# led_2835_curve_45X45cm.net
KiCad netlist of a schematic drawn in Altium Designer
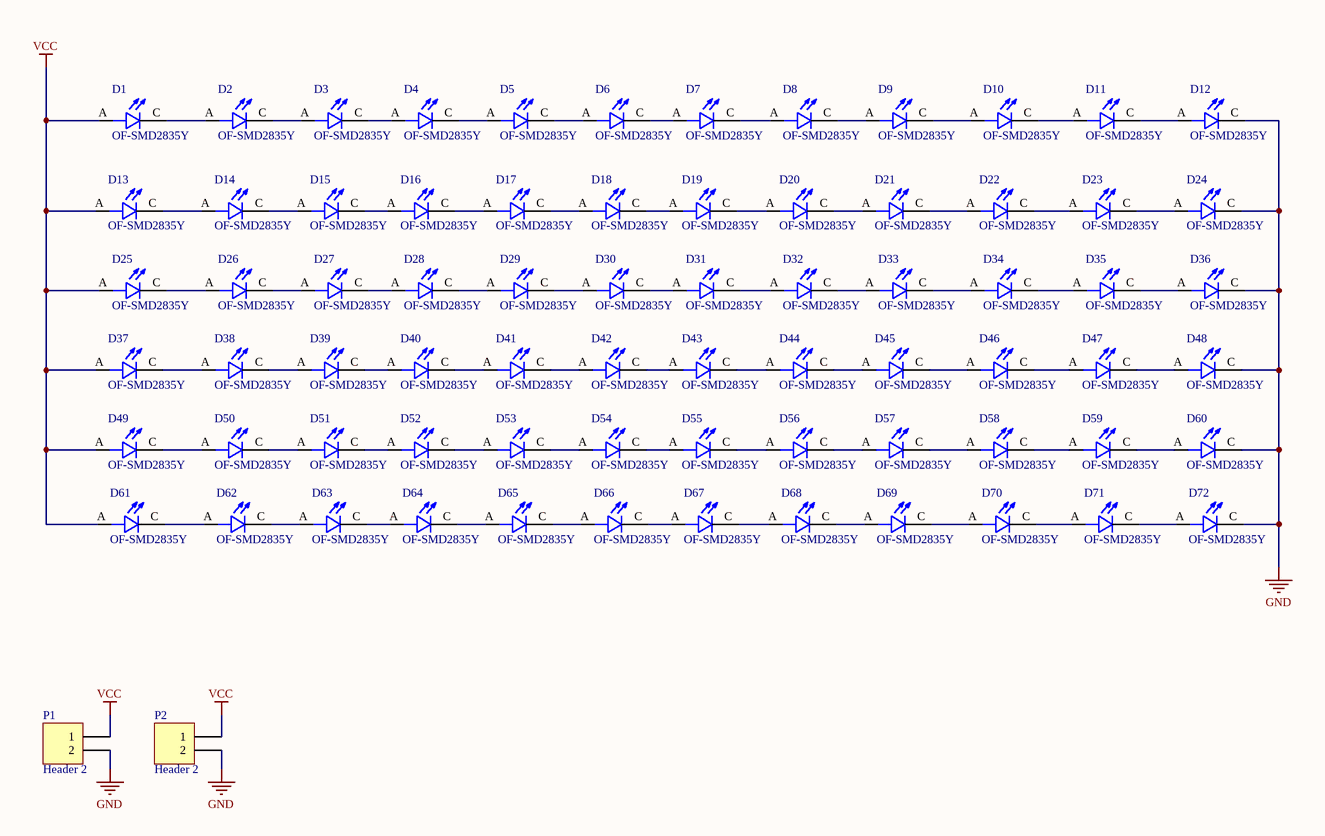
[diagram p0: led_2835_curve_45X45cm.SchDoc]

(export (version "E")
  (design (tool "Eeschema 10.0.6"))
  (components
    (comp (ref "D1")
      (value "OF-SMD2835Y")
      (footprint "LED_OF-SMD2835Y")
      (description "LED; SMD; 2835, PLCC2; yellow; 2200-2800mcd; 2.8x3.5x0.75mm; 120Â°")
      (libsource (lib "") (part "OF-SMD2835Y_3"))
    )
    (comp (ref "D2")
      (value "OF-SMD2835Y")
      (footprint "LED_OF-SMD2835Y")
      (description "LED; SMD; 2835, PLCC2; yellow; 2200-2800mcd; 2.8x3.5x0.75mm; 120Â°")
      (libsource (lib "") (part "OF-SMD2835Y_3"))
    )
    (comp (ref "D3")
      (value "OF-SMD2835Y")
      (footprint "LED_OF-SMD2835Y")
      (description "LED; SMD; 2835, PLCC2; yellow; 2200-2800mcd; 2.8x3.5x0.75mm; 120Â°")
      (libsource (lib "") (part "OF-SMD2835Y_3"))
    )
    (comp (ref "D4")
      (value "OF-SMD2835Y")
      (footprint "LED_OF-SMD2835Y")
      (description "LED; SMD; 2835, PLCC2; yellow; 2200-2800mcd; 2.8x3.5x0.75mm; 120Â°")
      (libsource (lib "") (part "OF-SMD2835Y_3"))
    )
    (comp (ref "D5")
      (value "OF-SMD2835Y")
      (footprint "LED_OF-SMD2835Y")
      (description "LED; SMD; 2835, PLCC2; yellow; 2200-2800mcd; 2.8x3.5x0.75mm; 120Â°")
      (libsource (lib "") (part "OF-SMD2835Y_3"))
    )
    (comp (ref "D6")
      (value "OF-SMD2835Y")
      (footprint "LED_OF-SMD2835Y")
      (description "LED; SMD; 2835, PLCC2; yellow; 2200-2800mcd; 2.8x3.5x0.75mm; 120Â°")
      (libsource (lib "") (part "OF-SMD2835Y_1"))
    )
    (comp (ref "D7")
      (value "OF-SMD2835Y")
      (footprint "LED_OF-SMD2835Y")
      (description "LED; SMD; 2835, PLCC2; yellow; 2200-2800mcd; 2.8x3.5x0.75mm; 120Â°")
      (libsource (lib "") (part "OF-SMD2835Y_1"))
    )
    (comp (ref "D8")
      (value "OF-SMD2835Y")
      (footprint "LED_OF-SMD2835Y")
      (description "LED; SMD; 2835, PLCC2; yellow; 2200-2800mcd; 2.8x3.5x0.75mm; 120Â°")
      (libsource (lib "") (part "OF-SMD2835Y_1"))
    )
    (comp (ref "D9")
      (value "OF-SMD2835Y")
      (footprint "LED_OF-SMD2835Y")
      (description "LED; SMD; 2835, PLCC2; yellow; 2200-2800mcd; 2.8x3.5x0.75mm; 120Â°")
      (libsource (lib "") (part "OF-SMD2835Y_1"))
    )
    (comp (ref "D10")
      (value "OF-SMD2835Y")
      (footprint "LED_OF-SMD2835Y")
      (description "LED; SMD; 2835, PLCC2; yellow; 2200-2800mcd; 2.8x3.5x0.75mm; 120Â°")
      (libsource (lib "") (part "OF-SMD2835Y_1"))
    )
    (comp (ref "D11")
      (value "OF-SMD2835Y")
      (footprint "LED_OF-SMD2835Y")
      (description "LED; SMD; 2835, PLCC2; yellow; 2200-2800mcd; 2.8x3.5x0.75mm; 120Â°")
      (libsource (lib "") (part "OF-SMD2835Y_1"))
    )
    (comp (ref "D12")
      (value "OF-SMD2835Y")
      (footprint "LED_OF-SMD2835Y")
      (description "LED; SMD; 2835, PLCC2; yellow; 2200-2800mcd; 2.8x3.5x0.75mm; 120Â°")
      (libsource (lib "") (part "OF-SMD2835Y_1"))
    )
    (comp (ref "D13")
      (value "OF-SMD2835Y")
      (footprint "LED_OF-SMD2835Y")
      (description "LED; SMD; 2835, PLCC2; yellow; 2200-2800mcd; 2.8x3.5x0.75mm; 120Â°")
      (libsource (lib "OF-SMD2835Y") (part "OF-SMD2835Y"))
    )
    (comp (ref "D14")
      (value "OF-SMD2835Y")
      (footprint "LED_OF-SMD2835Y")
      (description "LED; SMD; 2835, PLCC2; yellow; 2200-2800mcd; 2.8x3.5x0.75mm; 120Â°")
      (libsource (lib "OF-SMD2835Y") (part "OF-SMD2835Y"))
    )
    (comp (ref "D15")
      (value "OF-SMD2835Y")
      (footprint "LED_OF-SMD2835Y")
      (description "LED; SMD; 2835, PLCC2; yellow; 2200-2800mcd; 2.8x3.5x0.75mm; 120Â°")
      (libsource (lib "OF-SMD2835Y") (part "OF-SMD2835Y"))
    )
    (comp (ref "D16")
      (value "OF-SMD2835Y")
      (footprint "LED_OF-SMD2835Y")
      (description "LED; SMD; 2835, PLCC2; yellow; 2200-2800mcd; 2.8x3.5x0.75mm; 120Â°")
      (libsource (lib "OF-SMD2835Y") (part "OF-SMD2835Y"))
    )
    (comp (ref "D17")
      (value "OF-SMD2835Y")
      (footprint "LED_OF-SMD2835Y")
      (description "LED; SMD; 2835, PLCC2; yellow; 2200-2800mcd; 2.8x3.5x0.75mm; 120Â°")
      (libsource (lib "OF-SMD2835Y") (part "OF-SMD2835Y"))
    )
    (comp (ref "D18")
      (value "OF-SMD2835Y")
      (footprint "LED_OF-SMD2835Y")
      (description "LED; SMD; 2835, PLCC2; yellow; 2200-2800mcd; 2.8x3.5x0.75mm; 120Â°")
      (libsource (lib "") (part "OF-SMD2835Y_2"))
    )
    (comp (ref "D19")
      (value "OF-SMD2835Y")
      (footprint "LED_OF-SMD2835Y")
      (description "LED; SMD; 2835, PLCC2; yellow; 2200-2800mcd; 2.8x3.5x0.75mm; 120Â°")
      (libsource (lib "") (part "OF-SMD2835Y_2"))
    )
    (comp (ref "D20")
      (value "OF-SMD2835Y")
      (footprint "LED_OF-SMD2835Y")
      (description "LED; SMD; 2835, PLCC2; yellow; 2200-2800mcd; 2.8x3.5x0.75mm; 120Â°")
      (libsource (lib "") (part "OF-SMD2835Y_2"))
    )
    (comp (ref "D21")
      (value "OF-SMD2835Y")
      (footprint "LED_OF-SMD2835Y")
      (description "LED; SMD; 2835, PLCC2; yellow; 2200-2800mcd; 2.8x3.5x0.75mm; 120Â°")
      (libsource (lib "") (part "OF-SMD2835Y_2"))
    )
    (comp (ref "D22")
      (value "OF-SMD2835Y")
      (footprint "LED_OF-SMD2835Y")
      (description "LED; SMD; 2835, PLCC2; yellow; 2200-2800mcd; 2.8x3.5x0.75mm; 120Â°")
      (libsource (lib "") (part "OF-SMD2835Y_2"))
    )
    (comp (ref "D23")
      (value "OF-SMD2835Y")
      (footprint "LED_OF-SMD2835Y")
      (description "LED; SMD; 2835, PLCC2; yellow; 2200-2800mcd; 2.8x3.5x0.75mm; 120Â°")
      (libsource (lib "") (part "OF-SMD2835Y_2"))
    )
    (comp (ref "D24")
      (value "OF-SMD2835Y")
      (footprint "LED_OF-SMD2835Y")
      (description "LED; SMD; 2835, PLCC2; yellow; 2200-2800mcd; 2.8x3.5x0.75mm; 120Â°")
      (libsource (lib "") (part "OF-SMD2835Y_2"))
    )
    (comp (ref "D25")
      (value "OF-SMD2835Y")
      (footprint "LED_OF-SMD2835Y")
      (description "LED; SMD; 2835, PLCC2; yellow; 2200-2800mcd; 2.8x3.5x0.75mm; 120Â°")
      (libsource (lib "OF-SMD2835Y") (part "OF-SMD2835Y"))
    )
    (comp (ref "D26")
      (value "OF-SMD2835Y")
      (footprint "LED_OF-SMD2835Y")
      (description "LED; SMD; 2835, PLCC2; yellow; 2200-2800mcd; 2.8x3.5x0.75mm; 120Â°")
      (libsource (lib "OF-SMD2835Y") (part "OF-SMD2835Y"))
    )
    (comp (ref "D27")
      (value "OF-SMD2835Y")
      (footprint "LED_OF-SMD2835Y")
      (description "LED; SMD; 2835, PLCC2; yellow; 2200-2800mcd; 2.8x3.5x0.75mm; 120Â°")
      (libsource (lib "OF-SMD2835Y") (part "OF-SMD2835Y"))
    )
    (comp (ref "D28")
      (value "OF-SMD2835Y")
      (footprint "LED_OF-SMD2835Y")
      (description "LED; SMD; 2835, PLCC2; yellow; 2200-2800mcd; 2.8x3.5x0.75mm; 120Â°")
      (libsource (lib "OF-SMD2835Y") (part "OF-SMD2835Y"))
    )
    (comp (ref "D29")
      (value "OF-SMD2835Y")
      (footprint "LED_OF-SMD2835Y")
      (description "LED; SMD; 2835, PLCC2; yellow; 2200-2800mcd; 2.8x3.5x0.75mm; 120Â°")
      (libsource (lib "OF-SMD2835Y") (part "OF-SMD2835Y"))
    )
    (comp (ref "D30")
      (value "OF-SMD2835Y")
      (footprint "LED_OF-SMD2835Y")
      (description "LED; SMD; 2835, PLCC2; yellow; 2200-2800mcd; 2.8x3.5x0.75mm; 120Â°")
      (libsource (lib "") (part "OF-SMD2835Y_2"))
    )
    (comp (ref "D31")
      (value "OF-SMD2835Y")
      (footprint "LED_OF-SMD2835Y")
      (description "LED; SMD; 2835, PLCC2; yellow; 2200-2800mcd; 2.8x3.5x0.75mm; 120Â°")
      (libsource (lib "") (part "OF-SMD2835Y_2"))
    )
    (comp (ref "D32")
      (value "OF-SMD2835Y")
      (footprint "LED_OF-SMD2835Y")
      (description "LED; SMD; 2835, PLCC2; yellow; 2200-2800mcd; 2.8x3.5x0.75mm; 120Â°")
      (libsource (lib "") (part "OF-SMD2835Y_2"))
    )
    (comp (ref "D33")
      (value "OF-SMD2835Y")
      (footprint "LED_OF-SMD2835Y")
      (description "LED; SMD; 2835, PLCC2; yellow; 2200-2800mcd; 2.8x3.5x0.75mm; 120Â°")
      (libsource (lib "") (part "OF-SMD2835Y_2"))
    )
    (comp (ref "D34")
      (value "OF-SMD2835Y")
      (footprint "LED_OF-SMD2835Y")
      (description "LED; SMD; 2835, PLCC2; yellow; 2200-2800mcd; 2.8x3.5x0.75mm; 120Â°")
      (libsource (lib "") (part "OF-SMD2835Y_2"))
    )
    (comp (ref "D35")
      (value "OF-SMD2835Y")
      (footprint "LED_OF-SMD2835Y")
      (description "LED; SMD; 2835, PLCC2; yellow; 2200-2800mcd; 2.8x3.5x0.75mm; 120Â°")
      (libsource (lib "") (part "OF-SMD2835Y_2"))
    )
    (comp (ref "D36")
      (value "OF-SMD2835Y")
      (footprint "LED_OF-SMD2835Y")
      (description "LED; SMD; 2835, PLCC2; yellow; 2200-2800mcd; 2.8x3.5x0.75mm; 120Â°")
      (libsource (lib "") (part "OF-SMD2835Y_2"))
    )
    (comp (ref "D37")
      (value "OF-SMD2835Y")
      (footprint "LED_OF-SMD2835Y")
      (description "LED; SMD; 2835, PLCC2; yellow; 2200-2800mcd; 2.8x3.5x0.75mm; 120Â°")
      (libsource (lib "OF-SMD2835Y") (part "OF-SMD2835Y"))
    )
    (comp (ref "D38")
      (value "OF-SMD2835Y")
      (footprint "LED_OF-SMD2835Y")
      (description "LED; SMD; 2835, PLCC2; yellow; 2200-2800mcd; 2.8x3.5x0.75mm; 120Â°")
      (libsource (lib "OF-SMD2835Y") (part "OF-SMD2835Y"))
    )
    (comp (ref "D39")
      (value "OF-SMD2835Y")
      (footprint "LED_OF-SMD2835Y")
      (description "LED; SMD; 2835, PLCC2; yellow; 2200-2800mcd; 2.8x3.5x0.75mm; 120Â°")
      (libsource (lib "OF-SMD2835Y") (part "OF-SMD2835Y"))
    )
    (comp (ref "D40")
      (value "OF-SMD2835Y")
      (footprint "LED_OF-SMD2835Y")
      (description "LED; SMD; 2835, PLCC2; yellow; 2200-2800mcd; 2.8x3.5x0.75mm; 120Â°")
      (libsource (lib "OF-SMD2835Y") (part "OF-SMD2835Y"))
    )
    (comp (ref "D41")
      (value "OF-SMD2835Y")
      (footprint "LED_OF-SMD2835Y")
      (description "LED; SMD; 2835, PLCC2; yellow; 2200-2800mcd; 2.8x3.5x0.75mm; 120Â°")
      (libsource (lib "OF-SMD2835Y") (part "OF-SMD2835Y"))
    )
    (comp (ref "D42")
      (value "OF-SMD2835Y")
      (footprint "LED_OF-SMD2835Y")
      (description "LED; SMD; 2835, PLCC2; yellow; 2200-2800mcd; 2.8x3.5x0.75mm; 120Â°")
      (libsource (lib "") (part "OF-SMD2835Y_2"))
    )
    (comp (ref "D43")
      (value "OF-SMD2835Y")
      (footprint "LED_OF-SMD2835Y")
      (description "LED; SMD; 2835, PLCC2; yellow; 2200-2800mcd; 2.8x3.5x0.75mm; 120Â°")
      (libsource (lib "") (part "OF-SMD2835Y_2"))
    )
    (comp (ref "D44")
      (value "OF-SMD2835Y")
      (footprint "LED_OF-SMD2835Y")
      (description "LED; SMD; 2835, PLCC2; yellow; 2200-2800mcd; 2.8x3.5x0.75mm; 120Â°")
      (libsource (lib "") (part "OF-SMD2835Y_2"))
    )
    (comp (ref "D45")
      (value "OF-SMD2835Y")
      (footprint "LED_OF-SMD2835Y")
      (description "LED; SMD; 2835, PLCC2; yellow; 2200-2800mcd; 2.8x3.5x0.75mm; 120Â°")
      (libsource (lib "") (part "OF-SMD2835Y_2"))
    )
    (comp (ref "D46")
      (value "OF-SMD2835Y")
      (footprint "LED_OF-SMD2835Y")
      (description "LED; SMD; 2835, PLCC2; yellow; 2200-2800mcd; 2.8x3.5x0.75mm; 120Â°")
      (libsource (lib "") (part "OF-SMD2835Y_2"))
    )
    (comp (ref "D47")
      (value "OF-SMD2835Y")
      (footprint "LED_OF-SMD2835Y")
      (description "LED; SMD; 2835, PLCC2; yellow; 2200-2800mcd; 2.8x3.5x0.75mm; 120Â°")
      (libsource (lib "") (part "OF-SMD2835Y_2"))
    )
    (comp (ref "D48")
      (value "OF-SMD2835Y")
      (footprint "LED_OF-SMD2835Y")
      (description "LED; SMD; 2835, PLCC2; yellow; 2200-2800mcd; 2.8x3.5x0.75mm; 120Â°")
      (libsource (lib "") (part "OF-SMD2835Y_2"))
    )
    (comp (ref "D49")
      (value "OF-SMD2835Y")
      (footprint "LED_OF-SMD2835Y")
      (description "LED; SMD; 2835, PLCC2; yellow; 2200-2800mcd; 2.8x3.5x0.75mm; 120Â°")
      (libsource (lib "OF-SMD2835Y") (part "OF-SMD2835Y"))
    )
    (comp (ref "D50")
      (value "OF-SMD2835Y")
      (footprint "LED_OF-SMD2835Y")
      (description "LED; SMD; 2835, PLCC2; yellow; 2200-2800mcd; 2.8x3.5x0.75mm; 120Â°")
      (libsource (lib "OF-SMD2835Y") (part "OF-SMD2835Y"))
    )
    (comp (ref "D51")
      (value "OF-SMD2835Y")
      (footprint "LED_OF-SMD2835Y")
      (description "LED; SMD; 2835, PLCC2; yellow; 2200-2800mcd; 2.8x3.5x0.75mm; 120Â°")
      (libsource (lib "OF-SMD2835Y") (part "OF-SMD2835Y"))
    )
    (comp (ref "D52")
      (value "OF-SMD2835Y")
      (footprint "LED_OF-SMD2835Y")
      (description "LED; SMD; 2835, PLCC2; yellow; 2200-2800mcd; 2.8x3.5x0.75mm; 120Â°")
      (libsource (lib "OF-SMD2835Y") (part "OF-SMD2835Y"))
    )
    (comp (ref "D53")
      (value "OF-SMD2835Y")
      (footprint "LED_OF-SMD2835Y")
      (description "LED; SMD; 2835, PLCC2; yellow; 2200-2800mcd; 2.8x3.5x0.75mm; 120Â°")
      (libsource (lib "OF-SMD2835Y") (part "OF-SMD2835Y"))
    )
    (comp (ref "D54")
      (value "OF-SMD2835Y")
      (footprint "LED_OF-SMD2835Y")
      (description "LED; SMD; 2835, PLCC2; yellow; 2200-2800mcd; 2.8x3.5x0.75mm; 120Â°")
      (libsource (lib "") (part "OF-SMD2835Y_2"))
    )
    (comp (ref "D55")
      (value "OF-SMD2835Y")
      (footprint "LED_OF-SMD2835Y")
      (description "LED; SMD; 2835, PLCC2; yellow; 2200-2800mcd; 2.8x3.5x0.75mm; 120Â°")
      (libsource (lib "") (part "OF-SMD2835Y_2"))
    )
    (comp (ref "D56")
      (value "OF-SMD2835Y")
      (footprint "LED_OF-SMD2835Y")
      (description "LED; SMD; 2835, PLCC2; yellow; 2200-2800mcd; 2.8x3.5x0.75mm; 120Â°")
      (libsource (lib "") (part "OF-SMD2835Y_2"))
    )
    (comp (ref "D57")
      (value "OF-SMD2835Y")
      (footprint "LED_OF-SMD2835Y")
      (description "LED; SMD; 2835, PLCC2; yellow; 2200-2800mcd; 2.8x3.5x0.75mm; 120Â°")
      (libsource (lib "") (part "OF-SMD2835Y_2"))
    )
    (comp (ref "D58")
      (value "OF-SMD2835Y")
      (footprint "LED_OF-SMD2835Y")
      (description "LED; SMD; 2835, PLCC2; yellow; 2200-2800mcd; 2.8x3.5x0.75mm; 120Â°")
      (libsource (lib "") (part "OF-SMD2835Y_2"))
    )
    (comp (ref "D59")
      (value "OF-SMD2835Y")
      (footprint "LED_OF-SMD2835Y")
      (description "LED; SMD; 2835, PLCC2; yellow; 2200-2800mcd; 2.8x3.5x0.75mm; 120Â°")
      (libsource (lib "") (part "OF-SMD2835Y_2"))
    )
    (comp (ref "D60")
      (value "OF-SMD2835Y")
      (footprint "LED_OF-SMD2835Y")
      (description "LED; SMD; 2835, PLCC2; yellow; 2200-2800mcd; 2.8x3.5x0.75mm; 120Â°")
      (libsource (lib "") (part "OF-SMD2835Y_2"))
    )
    (comp (ref "D61")
      (value "OF-SMD2835Y")
      (footprint "LED_OF-SMD2835Y")
      (description "LED; SMD; 2835, PLCC2; yellow; 2200-2800mcd; 2.8x3.5x0.75mm; 120Â°")
      (libsource (lib "OF-SMD2835Y") (part "OF-SMD2835Y"))
    )
    (comp (ref "D62")
      (value "OF-SMD2835Y")
      (footprint "LED_OF-SMD2835Y")
      (description "LED; SMD; 2835, PLCC2; yellow; 2200-2800mcd; 2.8x3.5x0.75mm; 120Â°")
      (libsource (lib "OF-SMD2835Y") (part "OF-SMD2835Y"))
    )
    (comp (ref "D63")
      (value "OF-SMD2835Y")
      (footprint "LED_OF-SMD2835Y")
      (description "LED; SMD; 2835, PLCC2; yellow; 2200-2800mcd; 2.8x3.5x0.75mm; 120Â°")
      (libsource (lib "OF-SMD2835Y") (part "OF-SMD2835Y"))
    )
    (comp (ref "D64")
      (value "OF-SMD2835Y")
      (footprint "LED_OF-SMD2835Y")
      (description "LED; SMD; 2835, PLCC2; yellow; 2200-2800mcd; 2.8x3.5x0.75mm; 120Â°")
      (libsource (lib "OF-SMD2835Y") (part "OF-SMD2835Y"))
    )
    (comp (ref "D65")
      (value "OF-SMD2835Y")
      (footprint "LED_OF-SMD2835Y")
      (description "LED; SMD; 2835, PLCC2; yellow; 2200-2800mcd; 2.8x3.5x0.75mm; 120Â°")
      (libsource (lib "OF-SMD2835Y") (part "OF-SMD2835Y"))
    )
    (comp (ref "D66")
      (value "OF-SMD2835Y")
      (footprint "LED_OF-SMD2835Y")
      (description "LED; SMD; 2835, PLCC2; yellow; 2200-2800mcd; 2.8x3.5x0.75mm; 120Â°")
      (libsource (lib "OF-SMD2835Y") (part "OF-SMD2835Y"))
    )
    (comp (ref "D67")
      (value "OF-SMD2835Y")
      (footprint "LED_OF-SMD2835Y")
      (description "LED; SMD; 2835, PLCC2; yellow; 2200-2800mcd; 2.8x3.5x0.75mm; 120Â°")
      (libsource (lib "") (part "OF-SMD2835Y_2"))
    )
    (comp (ref "D68")
      (value "OF-SMD2835Y")
      (footprint "LED_OF-SMD2835Y")
      (description "LED; SMD; 2835, PLCC2; yellow; 2200-2800mcd; 2.8x3.5x0.75mm; 120Â°")
      (libsource (lib "") (part "OF-SMD2835Y_2"))
    )
    (comp (ref "D69")
      (value "OF-SMD2835Y")
      (footprint "LED_OF-SMD2835Y")
      (description "LED; SMD; 2835, PLCC2; yellow; 2200-2800mcd; 2.8x3.5x0.75mm; 120Â°")
      (libsource (lib "") (part "OF-SMD2835Y_2"))
    )
    (comp (ref "D70")
      (value "OF-SMD2835Y")
      (footprint "LED_OF-SMD2835Y")
      (description "LED; SMD; 2835, PLCC2; yellow; 2200-2800mcd; 2.8x3.5x0.75mm; 120Â°")
      (libsource (lib "") (part "OF-SMD2835Y_2"))
    )
    (comp (ref "D71")
      (value "OF-SMD2835Y")
      (footprint "LED_OF-SMD2835Y")
      (description "LED; SMD; 2835, PLCC2; yellow; 2200-2800mcd; 2.8x3.5x0.75mm; 120Â°")
      (libsource (lib "") (part "OF-SMD2835Y_2"))
    )
    (comp (ref "D72")
      (value "OF-SMD2835Y")
      (footprint "LED_OF-SMD2835Y")
      (description "LED; SMD; 2835, PLCC2; yellow; 2200-2800mcd; 2.8x3.5x0.75mm; 120Â°")
      (libsource (lib "") (part "OF-SMD2835Y_2"))
    )
    (comp (ref "P1")
      (value "Header 2")
      (footprint "HDR1X2_SMD")
      (description "Header, 2-Pin")
      (fields (field (name "PUBLISHER") "Altium Limited"))
      (libsource (lib "Miscellaneous Connectors") (part "Header 2"))
    )
    (comp (ref "P2")
      (value "Header 2")
      (footprint "HDR1X2_SMD")
      (description "Header, 2-Pin")
      (fields (field (name "PUBLISHER") "Altium Limited"))
      (libsource (lib "Miscellaneous Connectors") (part "Header 2"))
    )
  )
  (nets
    (net (code "1") (name "GND") (class "Default")
      (node (ref "D12") (pin "C") (pinfunction "C_C") (pintype "passive"))
      (node (ref "D24") (pin "C") (pinfunction "C_C") (pintype "passive"))
      (node (ref "D36") (pin "C") (pinfunction "C_C") (pintype "passive"))
      (node (ref "D48") (pin "C") (pinfunction "C_C") (pintype "passive"))
      (node (ref "D60") (pin "C") (pinfunction "C_C") (pintype "passive"))
      (node (ref "D72") (pin "C") (pinfunction "C_C") (pintype "passive"))
      (node (ref "P1") (pin "2") (pinfunction "2_2") (pintype "passive"))
      (node (ref "P2") (pin "2") (pinfunction "2_2") (pintype "passive"))
    )
    (net (code "2") (name "Net-(D1-PadC)") (class "Default")
      (node (ref "D1") (pin "C") (pinfunction "C_C") (pintype "passive"))
      (node (ref "D2") (pin "A") (pinfunction "A_A") (pintype "passive"))
    )
    (net (code "3") (name "Net-(D2-PadC)") (class "Default")
      (node (ref "D2") (pin "C") (pinfunction "C_C") (pintype "passive"))
      (node (ref "D3") (pin "A") (pinfunction "A_A") (pintype "passive"))
    )
    (net (code "4") (name "Net-(D3-PadC)") (class "Default")
      (node (ref "D3") (pin "C") (pinfunction "C_C") (pintype "passive"))
      (node (ref "D4") (pin "A") (pinfunction "A_A") (pintype "passive"))
    )
    (net (code "5") (name "Net-(D4-PadC)") (class "Default")
      (node (ref "D4") (pin "C") (pinfunction "C_C") (pintype "passive"))
      (node (ref "D5") (pin "A") (pinfunction "A_A") (pintype "passive"))
    )
    (net (code "6") (name "Net-(D5-PadC)") (class "Default")
      (node (ref "D5") (pin "C") (pinfunction "C_C") (pintype "passive"))
      (node (ref "D6") (pin "A") (pinfunction "A_A") (pintype "passive"))
    )
    (net (code "7") (name "Net-(D6-PadC)") (class "Default")
      (node (ref "D6") (pin "C") (pinfunction "C_C") (pintype "passive"))
      (node (ref "D7") (pin "A") (pinfunction "A_A") (pintype "passive"))
    )
    (net (code "8") (name "Net-(D7-PadC)") (class "Default")
      (node (ref "D7") (pin "C") (pinfunction "C_C") (pintype "passive"))
      (node (ref "D8") (pin "A") (pinfunction "A_A") (pintype "passive"))
    )
    (net (code "9") (name "Net-(D8-PadC)") (class "Default")
      (node (ref "D8") (pin "C") (pinfunction "C_C") (pintype "passive"))
      (node (ref "D9") (pin "A") (pinfunction "A_A") (pintype "passive"))
    )
    (net (code "10") (name "Net-(D10-PadA)") (class "Default")
      (node (ref "D10") (pin "A") (pinfunction "A_A") (pintype "passive"))
      (node (ref "D9") (pin "C") (pinfunction "C_C") (pintype "passive"))
    )
    (net (code "11") (name "Net-(D10-PadC)") (class "Default")
      (node (ref "D10") (pin "C") (pinfunction "C_C") (pintype "passive"))
      (node (ref "D11") (pin "A") (pinfunction "A_A") (pintype "passive"))
    )
    (net (code "12") (name "Net-(D11-PadC)") (class "Default")
      (node (ref "D11") (pin "C") (pinfunction "C_C") (pintype "passive"))
      (node (ref "D12") (pin "A") (pinfunction "A_A") (pintype "passive"))
    )
    (net (code "13") (name "Net-(D13-PadC)") (class "Default")
      (node (ref "D13") (pin "C") (pinfunction "C_C") (pintype "passive"))
      (node (ref "D14") (pin "A") (pinfunction "A_A") (pintype "passive"))
    )
    (net (code "14") (name "Net-(D14-PadC)") (class "Default")
      (node (ref "D14") (pin "C") (pinfunction "C_C") (pintype "passive"))
      (node (ref "D15") (pin "A") (pinfunction "A_A") (pintype "passive"))
    )
    (net (code "15") (name "Net-(D15-PadC)") (class "Default")
      (node (ref "D15") (pin "C") (pinfunction "C_C") (pintype "passive"))
      (node (ref "D16") (pin "A") (pinfunction "A_A") (pintype "passive"))
    )
    (net (code "16") (name "Net-(D16-PadC)") (class "Default")
      (node (ref "D16") (pin "C") (pinfunction "C_C") (pintype "passive"))
      (node (ref "D17") (pin "A") (pinfunction "A_A") (pintype "passive"))
    )
    (net (code "17") (name "Net-(D17-PadC)") (class "Default")
      (node (ref "D17") (pin "C") (pinfunction "C_C") (pintype "passive"))
      (node (ref "D18") (pin "A") (pinfunction "A_A") (pintype "passive"))
    )
    (net (code "18") (name "Net-(D18-PadC)") (class "Default")
      (node (ref "D18") (pin "C") (pinfunction "C_C") (pintype "passive"))
      (node (ref "D19") (pin "A") (pinfunction "A_A") (pintype "passive"))
    )
    (net (code "19") (name "Net-(D19-PadC)") (class "Default")
      (node (ref "D19") (pin "C") (pinfunction "C_C") (pintype "passive"))
      (node (ref "D20") (pin "A") (pinfunction "A_A") (pintype "passive"))
    )
    (net (code "20") (name "Net-(D20-PadC)") (class "Default")
      (node (ref "D20") (pin "C") (pinfunction "C_C") (pintype "passive"))
      (node (ref "D21") (pin "A") (pinfunction "A_A") (pintype "passive"))
    )
    (net (code "21") (name "Net-(D21-PadC)") (class "Default")
      (node (ref "D21") (pin "C") (pinfunction "C_C") (pintype "passive"))
      (node (ref "D22") (pin "A") (pinfunction "A_A") (pintype "passive"))
    )
    (net (code "22") (name "Net-(D22-PadC)") (class "Default")
      (node (ref "D22") (pin "C") (pinfunction "C_C") (pintype "passive"))
      (node (ref "D23") (pin "A") (pinfunction "A_A") (pintype "passive"))
    )
    (net (code "23") (name "Net-(D23-PadC)") (class "Default")
      (node (ref "D23") (pin "C") (pinfunction "C_C") (pintype "passive"))
      (node (ref "D24") (pin "A") (pinfunction "A_A") (pintype "passive"))
    )
    (net (code "24") (name "Net-(D25-PadC)") (class "Default")
      (node (ref "D25") (pin "C") (pinfunction "C_C") (pintype "passive"))
      (node (ref "D26") (pin "A") (pinfunction "A_A") (pintype "passive"))
    )
    (net (code "25") (name "Net-(D26-PadC)") (class "Default")
      (node (ref "D26") (pin "C") (pinfunction "C_C") (pintype "passive"))
      (node (ref "D27") (pin "A") (pinfunction "A_A") (pintype "passive"))
    )
    (net (code "26") (name "Net-(D27-PadC)") (class "Default")
      (node (ref "D27") (pin "C") (pinfunction "C_C") (pintype "passive"))
      (node (ref "D28") (pin "A") (pinfunction "A_A") (pintype "passive"))
    )
    (net (code "27") (name "Net-(D28-PadC)") (class "Default")
      (node (ref "D28") (pin "C") (pinfunction "C_C") (pintype "passive"))
      (node (ref "D29") (pin "A") (pinfunction "A_A") (pintype "passive"))
    )
    (net (code "28") (name "Net-(D29-PadC)") (class "Default")
      (node (ref "D29") (pin "C") (pinfunction "C_C") (pintype "passive"))
      (node (ref "D30") (pin "A") (pinfunction "A_A") (pintype "passive"))
    )
    (net (code "29") (name "Net-(D30-PadC)") (class "Default")
      (node (ref "D30") (pin "C") (pinfunction "C_C") (pintype "passive"))
      (node (ref "D31") (pin "A") (pinfunction "A_A") (pintype "passive"))
    )
    (net (code "30") (name "Net-(D31-PadC)") (class "Default")
      (node (ref "D31") (pin "C") (pinfunction "C_C") (pintype "passive"))
      (node (ref "D32") (pin "A") (pinfunction "A_A") (pintype "passive"))
    )
    (net (code "31") (name "Net-(D32-PadC)") (class "Default")
      (node (ref "D32") (pin "C") (pinfunction "C_C") (pintype "passive"))
      (node (ref "D33") (pin "A") (pinfunction "A_A") (pintype "passive"))
    )
    (net (code "32") (name "Net-(D33-PadC)") (class "Default")
      (node (ref "D33") (pin "C") (pinfunction "C_C") (pintype "passive"))
      (node (ref "D34") (pin "A") (pinfunction "A_A") (pintype "passive"))
    )
    (net (code "33") (name "Net-(D34-PadC)") (class "Default")
      (node (ref "D34") (pin "C") (pinfunction "C_C") (pintype "passive"))
      (node (ref "D35") (pin "A") (pinfunction "A_A") (pintype "passive"))
    )
    (net (code "34") (name "Net-(D35-PadC)") (class "Default")
      (node (ref "D35") (pin "C") (pinfunction "C_C") (pintype "passive"))
      (node (ref "D36") (pin "A") (pinfunction "A_A") (pintype "passive"))
    )
    (net (code "35") (name "Net-(D37-PadC)") (class "Default")
      (node (ref "D37") (pin "C") (pinfunction "C_C") (pintype "passive"))
      (node (ref "D38") (pin "A") (pinfunction "A_A") (pintype "passive"))
    )
    (net (code "36") (name "Net-(D38-PadC)") (class "Default")
      (node (ref "D38") (pin "C") (pinfunction "C_C") (pintype "passive"))
      (node (ref "D39") (pin "A") (pinfunction "A_A") (pintype "passive"))
    )
    (net (code "37") (name "Net-(D39-PadC)") (class "Default")
      (node (ref "D39") (pin "C") (pinfunction "C_C") (pintype "passive"))
      (node (ref "D40") (pin "A") (pinfunction "A_A") (pintype "passive"))
    )
    (net (code "38") (name "Net-(D40-PadC)") (class "Default")
      (node (ref "D40") (pin "C") (pinfunction "C_C") (pintype "passive"))
      (node (ref "D41") (pin "A") (pinfunction "A_A") (pintype "passive"))
    )
    (net (code "39") (name "Net-(D41-PadC)") (class "Default")
      (node (ref "D41") (pin "C") (pinfunction "C_C") (pintype "passive"))
      (node (ref "D42") (pin "A") (pinfunction "A_A") (pintype "passive"))
    )
    (net (code "40") (name "Net-(D42-PadC)") (class "Default")
      (node (ref "D42") (pin "C") (pinfunction "C_C") (pintype "passive"))
      (node (ref "D43") (pin "A") (pinfunction "A_A") (pintype "passive"))
    )
    (net (code "41") (name "Net-(D43-PadC)") (class "Default")
      (node (ref "D43") (pin "C") (pinfunction "C_C") (pintype "passive"))
      (node (ref "D44") (pin "A") (pinfunction "A_A") (pintype "passive"))
    )
    (net (code "42") (name "Net-(D44-PadC)") (class "Default")
      (node (ref "D44") (pin "C") (pinfunction "C_C") (pintype "passive"))
      (node (ref "D45") (pin "A") (pinfunction "A_A") (pintype "passive"))
    )
    (net (code "43") (name "Net-(D45-PadC)") (class "Default")
      (node (ref "D45") (pin "C") (pinfunction "C_C") (pintype "passive"))
      (node (ref "D46") (pin "A") (pinfunction "A_A") (pintype "passive"))
    )
    (net (code "44") (name "Net-(D46-PadC)") (class "Default")
      (node (ref "D46") (pin "C") (pinfunction "C_C") (pintype "passive"))
      (node (ref "D47") (pin "A") (pinfunction "A_A") (pintype "passive"))
    )
    (net (code "45") (name "Net-(D47-PadC)") (class "Default")
      (node (ref "D47") (pin "C") (pinfunction "C_C") (pintype "passive"))
      (node (ref "D48") (pin "A") (pinfunction "A_A") (pintype "passive"))
    )
    (net (code "46") (name "Net-(D49-PadC)") (class "Default")
      (node (ref "D49") (pin "C") (pinfunction "C_C") (pintype "passive"))
      (node (ref "D50") (pin "A") (pinfunction "A_A") (pintype "passive"))
    )
    (net (code "47") (name "Net-(D50-PadC)") (class "Default")
      (node (ref "D50") (pin "C") (pinfunction "C_C") (pintype "passive"))
      (node (ref "D51") (pin "A") (pinfunction "A_A") (pintype "passive"))
    )
    (net (code "48") (name "Net-(D51-PadC)") (class "Default")
      (node (ref "D51") (pin "C") (pinfunction "C_C") (pintype "passive"))
      (node (ref "D52") (pin "A") (pinfunction "A_A") (pintype "passive"))
    )
    (net (code "49") (name "Net-(D52-PadC)") (class "Default")
      (node (ref "D52") (pin "C") (pinfunction "C_C") (pintype "passive"))
      (node (ref "D53") (pin "A") (pinfunction "A_A") (pintype "passive"))
    )
    (net (code "50") (name "Net-(D53-PadC)") (class "Default")
      (node (ref "D53") (pin "C") (pinfunction "C_C") (pintype "passive"))
      (node (ref "D54") (pin "A") (pinfunction "A_A") (pintype "passive"))
    )
    (net (code "51") (name "Net-(D54-PadC)") (class "Default")
      (node (ref "D54") (pin "C") (pinfunction "C_C") (pintype "passive"))
      (node (ref "D55") (pin "A") (pinfunction "A_A") (pintype "passive"))
    )
    (net (code "52") (name "Net-(D55-PadC)") (class "Default")
      (node (ref "D55") (pin "C") (pinfunction "C_C") (pintype "passive"))
      (node (ref "D56") (pin "A") (pinfunction "A_A") (pintype "passive"))
    )
    (net (code "53") (name "Net-(D56-PadC)") (class "Default")
      (node (ref "D56") (pin "C") (pinfunction "C_C") (pintype "passive"))
      (node (ref "D57") (pin "A") (pinfunction "A_A") (pintype "passive"))
    )
    (net (code "54") (name "Net-(D57-PadC)") (class "Default")
      (node (ref "D57") (pin "C") (pinfunction "C_C") (pintype "passive"))
      (node (ref "D58") (pin "A") (pinfunction "A_A") (pintype "passive"))
    )
    (net (code "55") (name "Net-(D58-PadC)") (class "Default")
      (node (ref "D58") (pin "C") (pinfunction "C_C") (pintype "passive"))
      (node (ref "D59") (pin "A") (pinfunction "A_A") (pintype "passive"))
    )
    (net (code "56") (name "Net-(D59-PadC)") (class "Default")
      (node (ref "D59") (pin "C") (pinfunction "C_C") (pintype "passive"))
      (node (ref "D60") (pin "A") (pinfunction "A_A") (pintype "passive"))
    )
    (net (code "57") (name "Net-(D61-PadC)") (class "Default")
      (node (ref "D61") (pin "C") (pinfunction "C_C") (pintype "passive"))
      (node (ref "D62") (pin "A") (pinfunction "A_A") (pintype "passive"))
    )
    (net (code "58") (name "Net-(D62-PadC)") (class "Default")
      (node (ref "D62") (pin "C") (pinfunction "C_C") (pintype "passive"))
      (node (ref "D63") (pin "A") (pinfunction "A_A") (pintype "passive"))
    )
    (net (code "59") (name "Net-(D63-PadC)") (class "Default")
      (node (ref "D63") (pin "C") (pinfunction "C_C") (pintype "passive"))
      (node (ref "D64") (pin "A") (pinfunction "A_A") (pintype "passive"))
    )
    (net (code "60") (name "Net-(D64-PadC)") (class "Default")
      (node (ref "D64") (pin "C") (pinfunction "C_C") (pintype "passive"))
      (node (ref "D65") (pin "A") (pinfunction "A_A") (pintype "passive"))
    )
    (net (code "61") (name "Net-(D65-PadC)") (class "Default")
      (node (ref "D65") (pin "C") (pinfunction "C_C") (pintype "passive"))
      (node (ref "D66") (pin "A") (pinfunction "A_A") (pintype "passive"))
    )
    (net (code "62") (name "Net-(D66-PadC)") (class "Default")
      (node (ref "D66") (pin "C") (pinfunction "C_C") (pintype "passive"))
      (node (ref "D67") (pin "A") (pinfunction "A_A") (pintype "passive"))
    )
    (net (code "63") (name "Net-(D67-PadC)") (class "Default")
      (node (ref "D67") (pin "C") (pinfunction "C_C") (pintype "passive"))
      (node (ref "D68") (pin "A") (pinfunction "A_A") (pintype "passive"))
    )
    (net (code "64") (name "Net-(D68-PadC)") (class "Default")
      (node (ref "D68") (pin "C") (pinfunction "C_C") (pintype "passive"))
      (node (ref "D69") (pin "A") (pinfunction "A_A") (pintype "passive"))
    )
    (net (code "65") (name "Net-(D69-PadC)") (class "Default")
      (node (ref "D69") (pin "C") (pinfunction "C_C") (pintype "passive"))
      (node (ref "D70") (pin "A") (pinfunction "A_A") (pintype "passive"))
    )
    (net (code "66") (name "Net-(D70-PadC)") (class "Default")
      (node (ref "D70") (pin "C") (pinfunction "C_C") (pintype "passive"))
      (node (ref "D71") (pin "A") (pinfunction "A_A") (pintype "passive"))
    )
    (net (code "67") (name "Net-(D71-PadC)") (class "Default")
      (node (ref "D71") (pin "C") (pinfunction "C_C") (pintype "passive"))
      (node (ref "D72") (pin "A") (pinfunction "A_A") (pintype "passive"))
    )
    (net (code "68") (name "VCC") (class "Default")
      (node (ref "D1") (pin "A") (pinfunction "A_A") (pintype "passive"))
      (node (ref "D13") (pin "A") (pinfunction "A_A") (pintype "passive"))
      (node (ref "D25") (pin "A") (pinfunction "A_A") (pintype "passive"))
      (node (ref "D37") (pin "A") (pinfunction "A_A") (pintype "passive"))
      (node (ref "D49") (pin "A") (pinfunction "A_A") (pintype "passive"))
      (node (ref "D61") (pin "A") (pinfunction "A_A") (pintype "passive"))
      (node (ref "P1") (pin "1") (pinfunction "1_1") (pintype "passive"))
      (node (ref "P2") (pin "1") (pinfunction "1_1") (pintype "passive"))
    )
  )
)
